# DMXextension.net
KiCad netlist of a schematic drawn in EAGLE
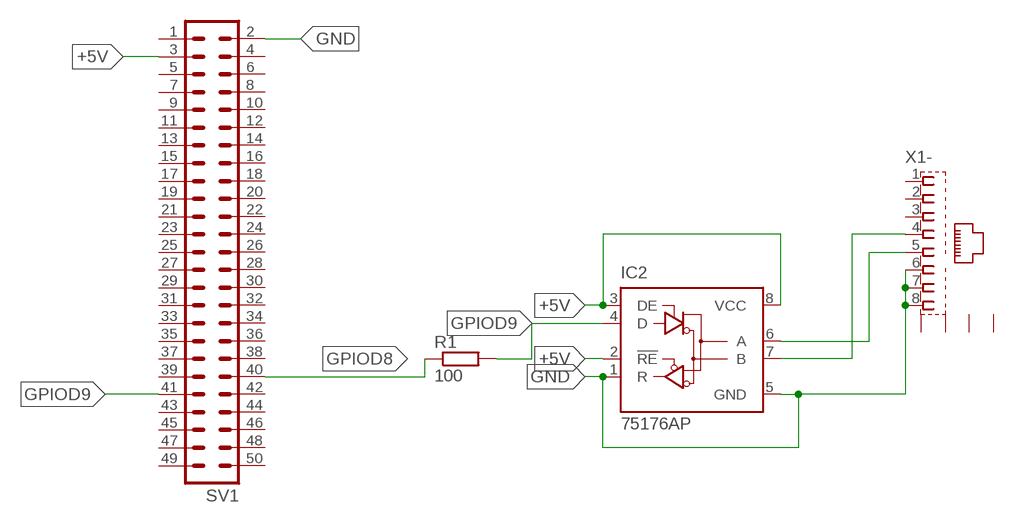
[diagram p0: schematic, sheet 1]

(export (version "E")
  (design (tool "Eeschema 10.0.6"))
  (components
    (comp (ref "IC2")
      (value "75176AP")
      (footprint "eagle-import:DIL08")
      (libsource (lib "eagle-import") (part "75176AP"))
    )
    (comp (ref "R1")
      (value "100")
      (footprint "eagle-import:R0805")
      (libsource (lib "eagle-import") (part "R-EU_R0805"))
    )
    (comp (ref "SV1")
      (value "ML50")
      (footprint "eagle-import:ML50")
      (libsource (lib "eagle-import") (part "ML50"))
    )
    (comp (ref "X1")
      (value "RJ45")
      (footprint "eagle-import:RJ45")
      (libsource (lib "eagle-import") (part "RJ45"))
    )
  )
  (nets
    (net (code "1") (name "+5V") (class "Default")
      (node (ref "IC2") (pin "2") (pinfunction "~{RE}_2") (pintype "input"))
      (node (ref "IC2") (pin "3") (pinfunction "DE_3") (pintype "input"))
      (node (ref "IC2") (pin "8") (pinfunction "VCC_8") (pintype "power_in"))
      (node (ref "SV1") (pin "3") (pinfunction "3_3") (pintype "passive"))
    )
    (net (code "2") (name "GND") (class "Default")
      (node (ref "IC2") (pin "1") (pinfunction "R_1") (pintype "input"))
      (node (ref "IC2") (pin "5") (pinfunction "GND_5") (pintype "power_in"))
      (node (ref "SV1") (pin "2") (pinfunction "2_2") (pintype "passive"))
      (node (ref "X1") (pin "6") (pinfunction "6_6") (pintype "passive"))
      (node (ref "X1") (pin "7") (pinfunction "7_7") (pintype "passive"))
      (node (ref "X1") (pin "8") (pinfunction "8_8") (pintype "passive"))
    )
    (net (code "3") (name "GPIOD8") (class "Default")
      (node (ref "R1") (pin "1") (pinfunction "1_1") (pintype "passive"))
      (node (ref "SV1") (pin "40") (pinfunction "40_40") (pintype "passive"))
    )
    (net (code "4") (name "GPIOD9") (class "Default")
      (node (ref "IC2") (pin "4") (pinfunction "D_4") (pintype "input"))
      (node (ref "R1") (pin "2") (pinfunction "2_2") (pintype "passive"))
      (node (ref "SV1") (pin "41") (pinfunction "41_41") (pintype "passive"))
    )
    (net (code "5") (name "Net-(IC2-A)") (class "Default")
      (node (ref "IC2") (pin "6") (pinfunction "A_6") (pintype "output"))
      (node (ref "X1") (pin "5") (pinfunction "5_5") (pintype "passive"))
    )
    (net (code "6") (name "Net-(IC2-B)") (class "Default")
      (node (ref "IC2") (pin "7") (pinfunction "B_7") (pintype "output"))
      (node (ref "X1") (pin "4") (pinfunction "4_4") (pintype "passive"))
    )
    (net (code "7") (name "unconnected-(SV1-Pad1)") (class "Default")
      (node (ref "SV1") (pin "1") (pinfunction "1_1") (pintype "passive"))
    )
    (net (code "8") (name "unconnected-(SV1-Pad4)") (class "Default")
      (node (ref "SV1") (pin "4") (pinfunction "4_4") (pintype "passive"))
    )
    (net (code "9") (name "unconnected-(SV1-Pad5)") (class "Default")
      (node (ref "SV1") (pin "5") (pinfunction "5_5") (pintype "passive"))
    )
    (net (code "10") (name "unconnected-(SV1-Pad6)") (class "Default")
      (node (ref "SV1") (pin "6") (pinfunction "6_6") (pintype "passive"))
    )
    (net (code "11") (name "unconnected-(SV1-Pad7)") (class "Default")
      (node (ref "SV1") (pin "7") (pinfunction "7_7") (pintype "passive"))
    )
    (net (code "12") (name "unconnected-(SV1-Pad8)") (class "Default")
      (node (ref "SV1") (pin "8") (pinfunction "8_8") (pintype "passive"))
    )
    (net (code "13") (name "unconnected-(SV1-Pad9)") (class "Default")
      (node (ref "SV1") (pin "9") (pinfunction "9_9") (pintype "passive"))
    )
    (net (code "14") (name "unconnected-(SV1-Pad10)") (class "Default")
      (node (ref "SV1") (pin "10") (pinfunction "10_10") (pintype "passive"))
    )
    (net (code "15") (name "unconnected-(SV1-Pad11)") (class "Default")
      (node (ref "SV1") (pin "11") (pinfunction "11_11") (pintype "passive"))
    )
    (net (code "16") (name "unconnected-(SV1-Pad12)") (class "Default")
      (node (ref "SV1") (pin "12") (pinfunction "12_12") (pintype "passive"))
    )
    (net (code "17") (name "unconnected-(SV1-Pad13)") (class "Default")
      (node (ref "SV1") (pin "13") (pinfunction "13_13") (pintype "passive"))
    )
    (net (code "18") (name "unconnected-(SV1-Pad14)") (class "Default")
      (node (ref "SV1") (pin "14") (pinfunction "14_14") (pintype "passive"))
    )
    (net (code "19") (name "unconnected-(SV1-Pad15)") (class "Default")
      (node (ref "SV1") (pin "15") (pinfunction "15_15") (pintype "passive"))
    )
    (net (code "20") (name "unconnected-(SV1-Pad16)") (class "Default")
      (node (ref "SV1") (pin "16") (pinfunction "16_16") (pintype "passive"))
    )
    (net (code "21") (name "unconnected-(SV1-Pad17)") (class "Default")
      (node (ref "SV1") (pin "17") (pinfunction "17_17") (pintype "passive"))
    )
    (net (code "22") (name "unconnected-(SV1-Pad18)") (class "Default")
      (node (ref "SV1") (pin "18") (pinfunction "18_18") (pintype "passive"))
    )
    (net (code "23") (name "unconnected-(SV1-Pad19)") (class "Default")
      (node (ref "SV1") (pin "19") (pinfunction "19_19") (pintype "passive"))
    )
    (net (code "24") (name "unconnected-(SV1-Pad20)") (class "Default")
      (node (ref "SV1") (pin "20") (pinfunction "20_20") (pintype "passive"))
    )
    (net (code "25") (name "unconnected-(SV1-Pad21)") (class "Default")
      (node (ref "SV1") (pin "21") (pinfunction "21_21") (pintype "passive"))
    )
    (net (code "26") (name "unconnected-(SV1-Pad22)") (class "Default")
      (node (ref "SV1") (pin "22") (pinfunction "22_22") (pintype "passive"))
    )
    (net (code "27") (name "unconnected-(SV1-Pad23)") (class "Default")
      (node (ref "SV1") (pin "23") (pinfunction "23_23") (pintype "passive"))
    )
    (net (code "28") (name "unconnected-(SV1-Pad24)") (class "Default")
      (node (ref "SV1") (pin "24") (pinfunction "24_24") (pintype "passive"))
    )
    (net (code "29") (name "unconnected-(SV1-Pad25)") (class "Default")
      (node (ref "SV1") (pin "25") (pinfunction "25_25") (pintype "passive"))
    )
    (net (code "30") (name "unconnected-(SV1-Pad26)") (class "Default")
      (node (ref "SV1") (pin "26") (pinfunction "26_26") (pintype "passive"))
    )
    (net (code "31") (name "unconnected-(SV1-Pad27)") (class "Default")
      (node (ref "SV1") (pin "27") (pinfunction "27_27") (pintype "passive"))
    )
    (net (code "32") (name "unconnected-(SV1-Pad28)") (class "Default")
      (node (ref "SV1") (pin "28") (pinfunction "28_28") (pintype "passive"))
    )
    (net (code "33") (name "unconnected-(SV1-Pad29)") (class "Default")
      (node (ref "SV1") (pin "29") (pinfunction "29_29") (pintype "passive"))
    )
    (net (code "34") (name "unconnected-(SV1-Pad30)") (class "Default")
      (node (ref "SV1") (pin "30") (pinfunction "30_30") (pintype "passive"))
    )
    (net (code "35") (name "unconnected-(SV1-Pad31)") (class "Default")
      (node (ref "SV1") (pin "31") (pinfunction "31_31") (pintype "passive"))
    )
    (net (code "36") (name "unconnected-(SV1-Pad32)") (class "Default")
      (node (ref "SV1") (pin "32") (pinfunction "32_32") (pintype "passive"))
    )
    (net (code "37") (name "unconnected-(SV1-Pad33)") (class "Default")
      (node (ref "SV1") (pin "33") (pinfunction "33_33") (pintype "passive"))
    )
    (net (code "38") (name "unconnected-(SV1-Pad34)") (class "Default")
      (node (ref "SV1") (pin "34") (pinfunction "34_34") (pintype "passive"))
    )
    (net (code "39") (name "unconnected-(SV1-Pad35)") (class "Default")
      (node (ref "SV1") (pin "35") (pinfunction "35_35") (pintype "passive"))
    )
    (net (code "40") (name "unconnected-(SV1-Pad36)") (class "Default")
      (node (ref "SV1") (pin "36") (pinfunction "36_36") (pintype "passive"))
    )
    (net (code "41") (name "unconnected-(SV1-Pad37)") (class "Default")
      (node (ref "SV1") (pin "37") (pinfunction "37_37") (pintype "passive"))
    )
    (net (code "42") (name "unconnected-(SV1-Pad38)") (class "Default")
      (node (ref "SV1") (pin "38") (pinfunction "38_38") (pintype "passive"))
    )
    (net (code "43") (name "unconnected-(SV1-Pad39)") (class "Default")
      (node (ref "SV1") (pin "39") (pinfunction "39_39") (pintype "passive"))
    )
    (net (code "44") (name "unconnected-(SV1-Pad42)") (class "Default")
      (node (ref "SV1") (pin "42") (pinfunction "42_42") (pintype "passive"))
    )
    (net (code "45") (name "unconnected-(SV1-Pad43)") (class "Default")
      (node (ref "SV1") (pin "43") (pinfunction "43_43") (pintype "passive"))
    )
    (net (code "46") (name "unconnected-(SV1-Pad44)") (class "Default")
      (node (ref "SV1") (pin "44") (pinfunction "44_44") (pintype "passive"))
    )
    (net (code "47") (name "unconnected-(SV1-Pad45)") (class "Default")
      (node (ref "SV1") (pin "45") (pinfunction "45_45") (pintype "passive"))
    )
    (net (code "48") (name "unconnected-(SV1-Pad46)") (class "Default")
      (node (ref "SV1") (pin "46") (pinfunction "46_46") (pintype "passive"))
    )
    (net (code "49") (name "unconnected-(SV1-Pad47)") (class "Default")
      (node (ref "SV1") (pin "47") (pinfunction "47_47") (pintype "passive"))
    )
    (net (code "50") (name "unconnected-(SV1-Pad48)") (class "Default")
      (node (ref "SV1") (pin "48") (pinfunction "48_48") (pintype "passive"))
    )
    (net (code "51") (name "unconnected-(SV1-Pad49)") (class "Default")
      (node (ref "SV1") (pin "49") (pinfunction "49_49") (pintype "passive"))
    )
    (net (code "52") (name "unconnected-(SV1-Pad50)") (class "Default")
      (node (ref "SV1") (pin "50") (pinfunction "50_50") (pintype "passive"))
    )
    (net (code "53") (name "unconnected-(X1-Pad1)") (class "Default")
      (node (ref "X1") (pin "1") (pinfunction "1_1") (pintype "passive"))
    )
    (net (code "54") (name "unconnected-(X1-Pad2)") (class "Default")
      (node (ref "X1") (pin "2") (pinfunction "2_2") (pintype "passive"))
    )
    (net (code "55") (name "unconnected-(X1-Pad3)") (class "Default")
      (node (ref "X1") (pin "3") (pinfunction "3_3") (pintype "passive"))
    )
    (net (code "56") (name "unconnected-(X1B-1-PadG1)") (class "Default")
      (node (ref "X1") (pin "G1") (pinfunction "1_G1") (pintype "passive"))
    )
    (net (code "57") (name "unconnected-(X1C-1-PadG2)") (class "Default")
      (node (ref "X1") (pin "G2") (pinfunction "1_G2") (pintype "passive"))
    )
    (net (code "58") (name "unconnected-(X1D-1-PadG3)") (class "Default")
      (node (ref "X1") (pin "G3") (pinfunction "1_G3") (pintype "passive"))
    )
    (net (code "59") (name "unconnected-(X1E-1-PadG4)") (class "Default")
      (node (ref "X1") (pin "G4") (pinfunction "1_G4") (pintype "passive"))
    )
  )
)
